# BRD161002.net
KiCad netlist of a schematic drawn in EAGLE
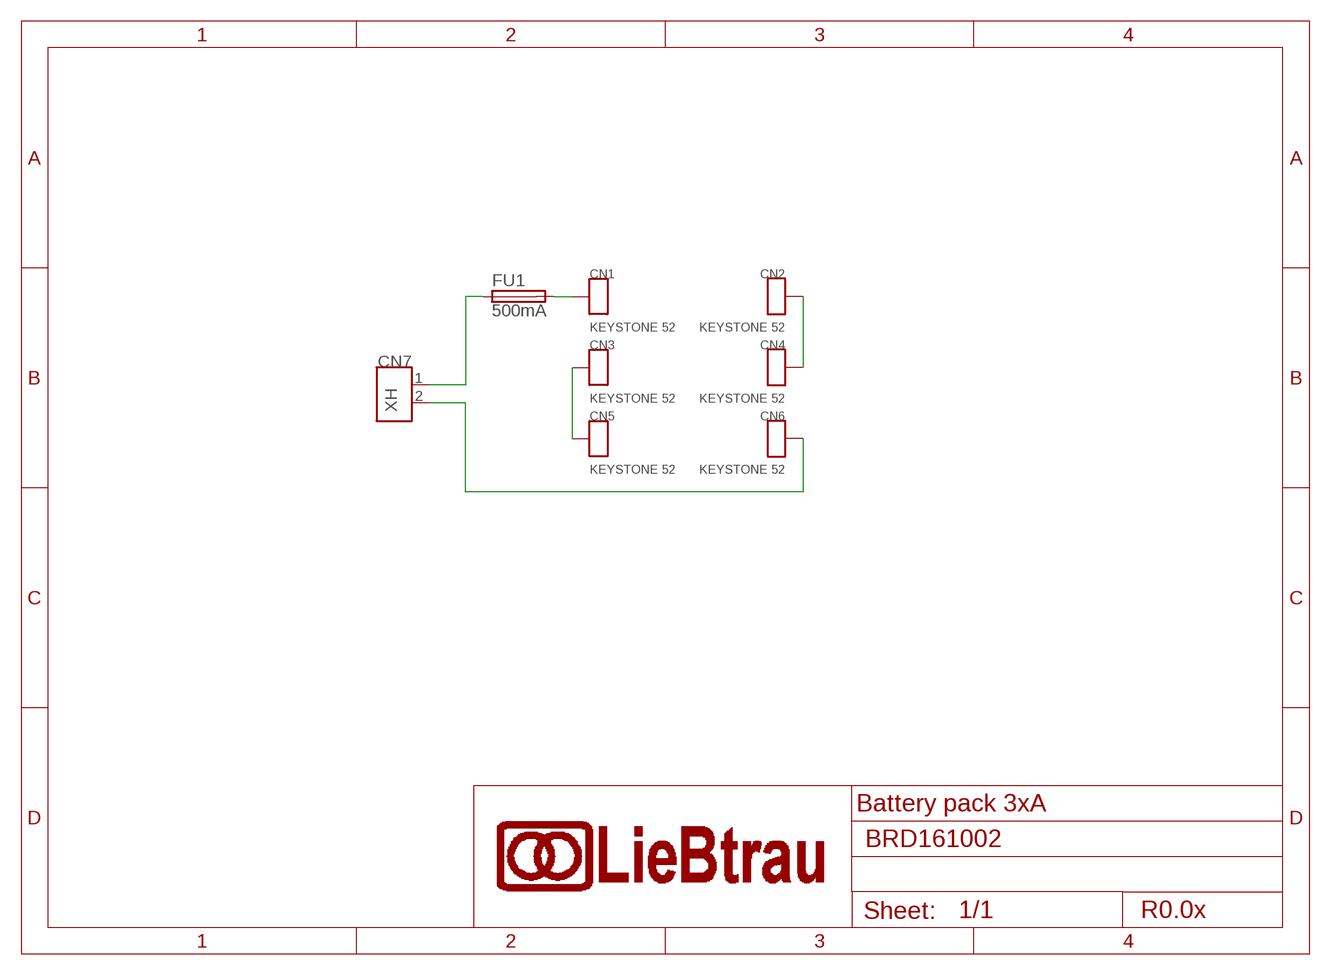
[diagram p0: schematic, sheet 1]

(export (version "E")
  (design (tool "Eeschema 10.0.6"))
  (components
    (comp (ref "CN1")
      (value "KEYSTONE 52")
      (footprint "eagle-import:CN_BATTERY_CLIP_A_AA")
      (libsource (lib "eagle-import") (part "CN_1PKEYSTONE_52_BATTERY_CLIP_A_AA_"))
    )
    (comp (ref "CN2")
      (value "KEYSTONE 52")
      (footprint "eagle-import:CN_BATTERY_CLIP_A_AA")
      (libsource (lib "eagle-import") (part "CN_1PKEYSTONE_52_BATTERY_CLIP_A_AA_"))
    )
    (comp (ref "CN3")
      (value "KEYSTONE 52")
      (footprint "eagle-import:CN_BATTERY_CLIP_A_AA")
      (libsource (lib "eagle-import") (part "CN_1PKEYSTONE_52_BATTERY_CLIP_A_AA_"))
    )
    (comp (ref "CN4")
      (value "KEYSTONE 52")
      (footprint "eagle-import:CN_BATTERY_CLIP_A_AA")
      (libsource (lib "eagle-import") (part "CN_1PKEYSTONE_52_BATTERY_CLIP_A_AA_"))
    )
    (comp (ref "CN5")
      (value "KEYSTONE 52")
      (footprint "eagle-import:CN_BATTERY_CLIP_A_AA")
      (libsource (lib "eagle-import") (part "CN_1PKEYSTONE_52_BATTERY_CLIP_A_AA_"))
    )
    (comp (ref "CN6")
      (value "KEYSTONE 52")
      (footprint "eagle-import:CN_BATTERY_CLIP_A_AA")
      (libsource (lib "eagle-import") (part "CN_1PKEYSTONE_52_BATTERY_CLIP_A_AA_"))
    )
    (comp (ref "CN7")
      (value "XH")
      (footprint "eagle-import:CN_HDR1X2_180D_P25_JST_B2B-XH")
      (libsource (lib "eagle-import") (part "CN_2PJST_B2B-XH_JST_B2B-XH_"))
    )
    (comp (ref "FU1")
      (value "500mA")
      (footprint "eagle-import:FU_1812")
      (libsource (lib "eagle-import") (part "FUFU_1812_POLY_500MA_"))
    )
  )
  (nets
    (net (code "1") (name "Net-(CN1-P$1-Pad1)") (class "Default")
      (node (ref "CN1") (pin "1") (pinfunction "P$1_1") (pintype "bidirectional"))
      (node (ref "CN1") (pin "2") (pinfunction "P$1_2") (pintype "bidirectional"))
      (node (ref "FU1") (pin "2") (pinfunction "2_2") (pintype "passive"))
    )
    (net (code "2") (name "Net-(CN2-P$1-Pad1)") (class "Default")
      (node (ref "CN2") (pin "1") (pinfunction "P$1_1") (pintype "bidirectional"))
      (node (ref "CN2") (pin "2") (pinfunction "P$1_2") (pintype "bidirectional"))
      (node (ref "CN4") (pin "1") (pinfunction "P$1_1") (pintype "bidirectional"))
      (node (ref "CN4") (pin "2") (pinfunction "P$1_2") (pintype "bidirectional"))
    )
    (net (code "3") (name "Net-(CN3-P$1-Pad1)") (class "Default")
      (node (ref "CN3") (pin "1") (pinfunction "P$1_1") (pintype "bidirectional"))
      (node (ref "CN3") (pin "2") (pinfunction "P$1_2") (pintype "bidirectional"))
      (node (ref "CN5") (pin "1") (pinfunction "P$1_1") (pintype "bidirectional"))
      (node (ref "CN5") (pin "2") (pinfunction "P$1_2") (pintype "bidirectional"))
    )
    (net (code "4") (name "Net-(CN6-P$1-Pad1)") (class "Default")
      (node (ref "CN6") (pin "1") (pinfunction "P$1_1") (pintype "bidirectional"))
      (node (ref "CN6") (pin "2") (pinfunction "P$1_2") (pintype "bidirectional"))
      (node (ref "CN7") (pin "2") (pinfunction "2_2") (pintype "bidirectional"))
    )
    (net (code "5") (name "Net-(CN7-Pad1)") (class "Default")
      (node (ref "CN7") (pin "1") (pinfunction "1_1") (pintype "bidirectional"))
      (node (ref "FU1") (pin "1") (pinfunction "1_1") (pintype "passive"))
    )
  )
)
